# SCH-Display_Sheet_2_Altium.net
KiCad netlist of a schematic drawn in Altium Designer
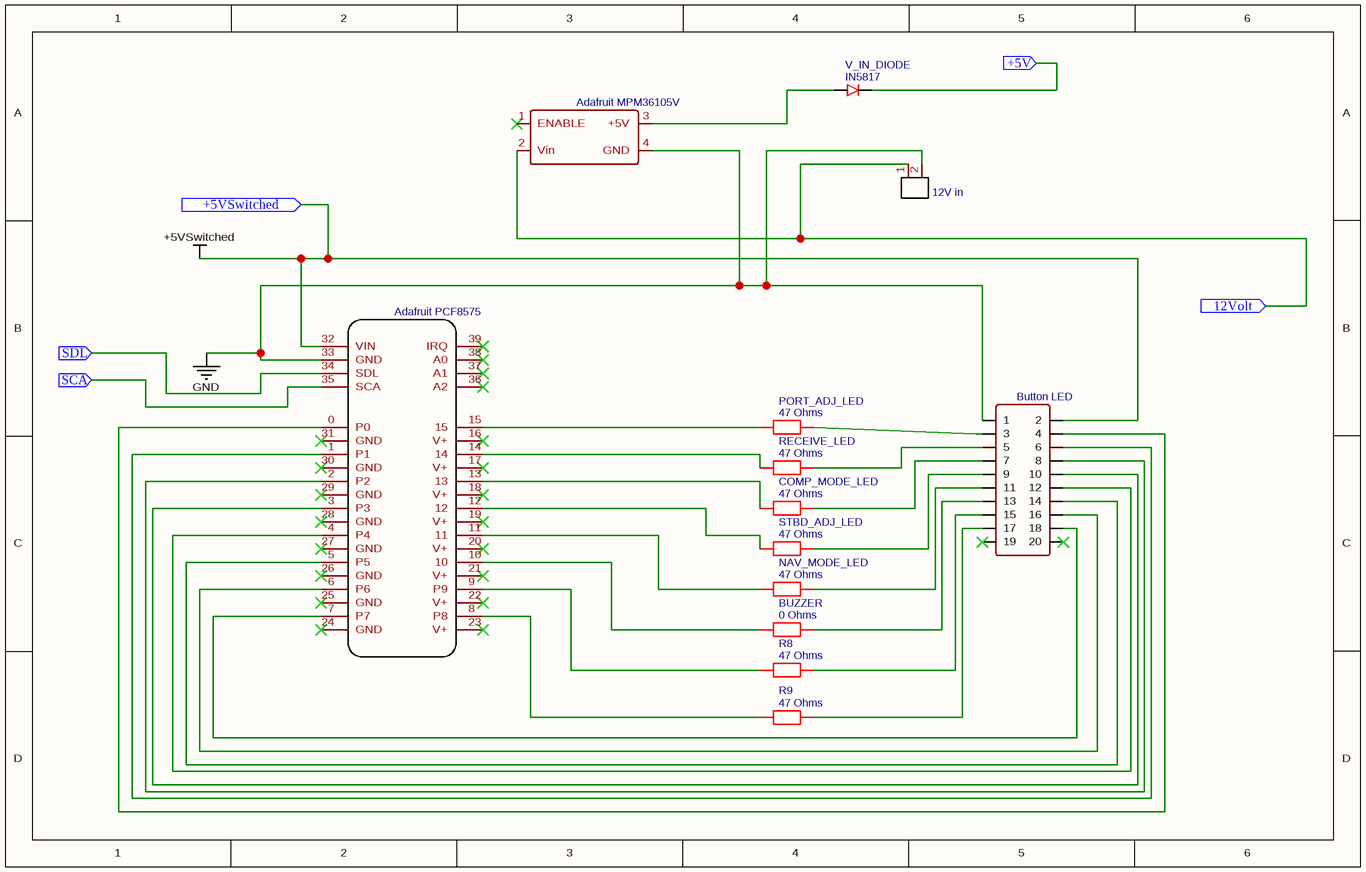
[diagram p0: SCH-Display_Sheet_2_Altium.schdoc]

(export (version "E")
  (design (tool "Eeschema 10.0.6"))
  (components
    (comp (ref "12V")
      (value "12V in")
      (fields (field (name "CONTRIBUTOR") "Grim Reaper (C0rbac)"))
      (libsource (lib "altium-import") (part "root_0_12V in_"))
    )
    (comp (ref "BUTTON_LED")
      (value "Button LED")
      (fields (field (name "CONTRIBUTOR") "LCEDA_Lib"))
      (libsource (lib "altium-import") (part "root_0_Button LED_"))
    )
    (comp (ref "BUZZER")
      (value "0 Ohms")
      (fields (field (name "CONTRIBUTOR") "Kagutsuchi"))
      (libsource (lib "altium-import") (part "root_0_0 Ohms_"))
    )
    (comp (ref "COMP_MODE_LED")
      (value "47 Ohms")
      (fields (field (name "CONTRIBUTOR") "Kagutsuchi"))
      (libsource (lib "altium-import") (part "root_0_47 Ohms_"))
    )
    (comp (ref "NAV_MODE_LED")
      (value "47 Ohms")
      (fields (field (name "CONTRIBUTOR") "Kagutsuchi"))
      (libsource (lib "altium-import") (part "root_0_47 Ohms_"))
    )
    (comp (ref "PORT_ADJ_LED")
      (value "47 Ohms")
      (fields (field (name "CONTRIBUTOR") "Kagutsuchi"))
      (libsource (lib "altium-import") (part "root_0_47 Ohms_"))
    )
    (comp (ref "R8")
      (value "47 Ohms")
      (fields (field (name "CONTRIBUTOR") "Kagutsuchi"))
      (libsource (lib "altium-import") (part "root_0_47 Ohms_"))
    )
    (comp (ref "R9")
      (value "47 Ohms")
      (fields (field (name "CONTRIBUTOR") "Kagutsuchi"))
      (libsource (lib "altium-import") (part "root_0_47 Ohms_"))
    )
    (comp (ref "RECEIVE_LED")
      (value "47 Ohms")
      (fields (field (name "CONTRIBUTOR") "Kagutsuchi"))
      (libsource (lib "altium-import") (part "root_0_47 Ohms_"))
    )
    (comp (ref "STBD_ADJ_LED")
      (value "47 Ohms")
      (fields (field (name "CONTRIBUTOR") "Kagutsuchi"))
      (libsource (lib "altium-import") (part "root_0_47 Ohms_"))
    )
    (comp (ref "U2")
      (value "Adafruit PCF8575")
      (fields (field (name "CONTRIBUTOR") "williambaucom"))
      (libsource (lib "altium-import") (part "root_3_Adafruit PCF8575_"))
    )
    (comp (ref "U5")
      (value "Adafruit MPM36105V")
      (fields (field (name "CONTRIBUTOR") "Aidan Farley"))
      (libsource (lib "altium-import") (part "root_0_Adafruit MPM36105V_"))
    )
    (comp (ref "V_IN_DIODE")
      (value "IN5817")
      (fields (field (name "MANUFACTURER PART") "DIODE") (field (name "CONTRIBUTOR") "mimit.oscar"))
      (libsource (lib "altium-import") (part "root_0_IN5817_"))
    )
  )
  (nets
    (net (code "1") (name "+5VSwitched") (class "Default")
      (node (ref "BUTTON_LED") (pin "2") (pinfunction "2_2") (pintype "passive"))
      (node (ref "U2") (pin "32") (pinfunction "VIN_32") (pintype "passive"))
    )
    (net (code "2") (name "/+5V") (class "Default")
      (node (ref "V_IN_DIODE") (pin "2") (pinfunction "2_2") (pintype "passive"))
    )
    (net (code "3") (name "/12Volt") (class "Default")
      (node (ref "12V") (pin "1") (pinfunction "1_1") (pintype "passive"))
      (node (ref "U5") (pin "2") (pinfunction "Vin_2") (pintype "passive"))
    )
    (net (code "4") (name "/SCA") (class "Default")
      (node (ref "U2") (pin "35") (pinfunction "SCA_35") (pintype "passive"))
    )
    (net (code "5") (name "/SDL") (class "Default")
      (node (ref "U2") (pin "34") (pinfunction "SDL_34") (pintype "passive"))
    )
    (net (code "6") (name "GND") (class "Default")
      (node (ref "12V") (pin "2") (pinfunction "2_2") (pintype "passive"))
      (node (ref "BUTTON_LED") (pin "1") (pinfunction "1_1") (pintype "passive"))
      (node (ref "U2") (pin "33") (pinfunction "GND_33") (pintype "passive"))
      (node (ref "U5") (pin "4") (pinfunction "GND_4") (pintype "passive"))
    )
    (net (code "7") (name "Net-(BUZZER-1)") (class "Default")
      (node (ref "BUTTON_LED") (pin "13") (pinfunction "13_13") (pintype "passive"))
      (node (ref "BUZZER") (pin "2") (pinfunction "1_2") (pintype "passive"))
    )
    (net (code "8") (name "Net-(BUZZER-2)") (class "Default")
      (node (ref "BUZZER") (pin "1") (pinfunction "2_1") (pintype "passive"))
      (node (ref "U2") (pin "10") (pinfunction "10_10") (pintype "passive"))
    )
    (net (code "9") (name "Net-(COMP_MODE_LED-1)") (class "Default")
      (node (ref "BUTTON_LED") (pin "7") (pinfunction "7_7") (pintype "passive"))
      (node (ref "COMP_MODE_LED") (pin "2") (pinfunction "1_2") (pintype "passive"))
    )
    (net (code "10") (name "Net-(COMP_MODE_LED-2)") (class "Default")
      (node (ref "COMP_MODE_LED") (pin "1") (pinfunction "2_1") (pintype "passive"))
      (node (ref "U2") (pin "13") (pinfunction "13_13") (pintype "passive"))
    )
    (net (code "11") (name "Net-(NAV_MODE_LED-1)") (class "Default")
      (node (ref "BUTTON_LED") (pin "11") (pinfunction "11_11") (pintype "passive"))
      (node (ref "NAV_MODE_LED") (pin "2") (pinfunction "1_2") (pintype "passive"))
    )
    (net (code "12") (name "Net-(NAV_MODE_LED-2)") (class "Default")
      (node (ref "NAV_MODE_LED") (pin "1") (pinfunction "2_1") (pintype "passive"))
      (node (ref "U2") (pin "11") (pinfunction "11_11") (pintype "passive"))
    )
    (net (code "13") (name "Net-(PORT_ADJ_LED-1)") (class "Default")
      (node (ref "BUTTON_LED") (pin "3") (pinfunction "3_3") (pintype "passive"))
      (node (ref "PORT_ADJ_LED") (pin "2") (pinfunction "1_2") (pintype "passive"))
    )
    (net (code "14") (name "Net-(PORT_ADJ_LED-2)") (class "Default")
      (node (ref "PORT_ADJ_LED") (pin "1") (pinfunction "2_1") (pintype "passive"))
      (node (ref "U2") (pin "15") (pinfunction "15_15") (pintype "passive"))
    )
    (net (code "15") (name "Net-(R8-1)") (class "Default")
      (node (ref "BUTTON_LED") (pin "15") (pinfunction "15_15") (pintype "passive"))
      (node (ref "R8") (pin "2") (pinfunction "1_2") (pintype "passive"))
    )
    (net (code "16") (name "Net-(R8-2)") (class "Default")
      (node (ref "R8") (pin "1") (pinfunction "2_1") (pintype "passive"))
      (node (ref "U2") (pin "9") (pinfunction "P9_9") (pintype "passive"))
    )
    (net (code "17") (name "Net-(R9-1)") (class "Default")
      (node (ref "BUTTON_LED") (pin "17") (pinfunction "17_17") (pintype "passive"))
      (node (ref "R9") (pin "2") (pinfunction "1_2") (pintype "passive"))
    )
    (net (code "18") (name "Net-(R9-2)") (class "Default")
      (node (ref "R9") (pin "1") (pinfunction "2_1") (pintype "passive"))
      (node (ref "U2") (pin "8") (pinfunction "P8_8") (pintype "passive"))
    )
    (net (code "19") (name "Net-(RECEIVE_LED-1)") (class "Default")
      (node (ref "BUTTON_LED") (pin "5") (pinfunction "5_5") (pintype "passive"))
      (node (ref "RECEIVE_LED") (pin "2") (pinfunction "1_2") (pintype "passive"))
    )
    (net (code "20") (name "Net-(RECEIVE_LED-2)") (class "Default")
      (node (ref "RECEIVE_LED") (pin "1") (pinfunction "2_1") (pintype "passive"))
      (node (ref "U2") (pin "14") (pinfunction "14_14") (pintype "passive"))
    )
    (net (code "21") (name "Net-(STBD_ADJ_LED-1)") (class "Default")
      (node (ref "BUTTON_LED") (pin "9") (pinfunction "9_9") (pintype "passive"))
      (node (ref "STBD_ADJ_LED") (pin "2") (pinfunction "1_2") (pintype "passive"))
    )
    (net (code "22") (name "Net-(STBD_ADJ_LED-2)") (class "Default")
      (node (ref "STBD_ADJ_LED") (pin "1") (pinfunction "2_1") (pintype "passive"))
      (node (ref "U2") (pin "12") (pinfunction "12_12") (pintype "passive"))
    )
    (net (code "23") (name "Net-(U2-P0)") (class "Default")
      (node (ref "BUTTON_LED") (pin "4") (pinfunction "4_4") (pintype "passive"))
      (node (ref "U2") (pin "0") (pinfunction "P0_0") (pintype "passive"))
    )
    (net (code "24") (name "Net-(U2-P1)") (class "Default")
      (node (ref "BUTTON_LED") (pin "6") (pinfunction "6_6") (pintype "passive"))
      (node (ref "U2") (pin "1") (pinfunction "P1_1") (pintype "passive"))
    )
    (net (code "25") (name "Net-(U2-P2)") (class "Default")
      (node (ref "BUTTON_LED") (pin "8") (pinfunction "8_8") (pintype "passive"))
      (node (ref "U2") (pin "2") (pinfunction "P2_2") (pintype "passive"))
    )
    (net (code "26") (name "Net-(U2-P3)") (class "Default")
      (node (ref "BUTTON_LED") (pin "10") (pinfunction "10_10") (pintype "passive"))
      (node (ref "U2") (pin "3") (pinfunction "P3_3") (pintype "passive"))
    )
    (net (code "27") (name "Net-(U2-P4)") (class "Default")
      (node (ref "BUTTON_LED") (pin "12") (pinfunction "12_12") (pintype "passive"))
      (node (ref "U2") (pin "4") (pinfunction "P4_4") (pintype "passive"))
    )
    (net (code "28") (name "Net-(U2-P5)") (class "Default")
      (node (ref "BUTTON_LED") (pin "14") (pinfunction "14_14") (pintype "passive"))
      (node (ref "U2") (pin "5") (pinfunction "P5_5") (pintype "passive"))
    )
    (net (code "29") (name "Net-(U2-P6)") (class "Default")
      (node (ref "BUTTON_LED") (pin "16") (pinfunction "16_16") (pintype "passive"))
      (node (ref "U2") (pin "6") (pinfunction "P6_6") (pintype "passive"))
    )
    (net (code "30") (name "Net-(U2-P7)") (class "Default")
      (node (ref "BUTTON_LED") (pin "18") (pinfunction "18_18") (pintype "passive"))
      (node (ref "U2") (pin "7") (pinfunction "P7_7") (pintype "passive"))
    )
    (net (code "31") (name "Net-(U5-+5V)") (class "Default")
      (node (ref "U5") (pin "3") (pinfunction "+5V_3") (pintype "passive"))
      (node (ref "V_IN_DIODE") (pin "1") (pinfunction "1_1") (pintype "passive"))
    )
    (net (code "32") (name "unconnected-(BUTTON_LED-Pad19)") (class "Default")
      (node (ref "BUTTON_LED") (pin "19") (pinfunction "19_19") (pintype "passive+no_connect"))
    )
    (net (code "33") (name "unconnected-(BUTTON_LED-Pad20)") (class "Default")
      (node (ref "BUTTON_LED") (pin "20") (pinfunction "20_20") (pintype "passive+no_connect"))
    )
    (net (code "34") (name "unconnected-(U2-A0-Pad38)") (class "Default")
      (node (ref "U2") (pin "38") (pinfunction "A0_38") (pintype "passive+no_connect"))
    )
    (net (code "35") (name "unconnected-(U2-A1-Pad37)") (class "Default")
      (node (ref "U2") (pin "37") (pinfunction "A1_37") (pintype "passive+no_connect"))
    )
    (net (code "36") (name "unconnected-(U2-A2-Pad36)") (class "Default")
      (node (ref "U2") (pin "36") (pinfunction "A2_36") (pintype "passive+no_connect"))
    )
    (net (code "37") (name "unconnected-(U2-GND-Pad24)") (class "Default")
      (node (ref "U2") (pin "24") (pinfunction "GND_24") (pintype "passive+no_connect"))
    )
    (net (code "38") (name "unconnected-(U2-GND-Pad25)") (class "Default")
      (node (ref "U2") (pin "25") (pinfunction "GND_25") (pintype "passive+no_connect"))
    )
    (net (code "39") (name "unconnected-(U2-GND-Pad26)") (class "Default")
      (node (ref "U2") (pin "26") (pinfunction "GND_26") (pintype "passive+no_connect"))
    )
    (net (code "40") (name "unconnected-(U2-GND-Pad27)") (class "Default")
      (node (ref "U2") (pin "27") (pinfunction "GND_27") (pintype "passive+no_connect"))
    )
    (net (code "41") (name "unconnected-(U2-GND-Pad28)") (class "Default")
      (node (ref "U2") (pin "28") (pinfunction "GND_28") (pintype "passive+no_connect"))
    )
    (net (code "42") (name "unconnected-(U2-GND-Pad29)") (class "Default")
      (node (ref "U2") (pin "29") (pinfunction "GND_29") (pintype "passive+no_connect"))
    )
    (net (code "43") (name "unconnected-(U2-GND-Pad30)") (class "Default")
      (node (ref "U2") (pin "30") (pinfunction "GND_30") (pintype "passive+no_connect"))
    )
    (net (code "44") (name "unconnected-(U2-GND-Pad31)") (class "Default")
      (node (ref "U2") (pin "31") (pinfunction "GND_31") (pintype "passive+no_connect"))
    )
    (net (code "45") (name "unconnected-(U2-IRQ-Pad39)") (class "Default")
      (node (ref "U2") (pin "39") (pinfunction "IRQ_39") (pintype "passive+no_connect"))
    )
    (net (code "46") (name "unconnected-(U2-V+-Pad16)") (class "Default")
      (node (ref "U2") (pin "16") (pinfunction "V+_16") (pintype "passive+no_connect"))
    )
    (net (code "47") (name "unconnected-(U2-V+-Pad17)") (class "Default")
      (node (ref "U2") (pin "17") (pinfunction "V+_17") (pintype "passive+no_connect"))
    )
    (net (code "48") (name "unconnected-(U2-V+-Pad18)") (class "Default")
      (node (ref "U2") (pin "18") (pinfunction "V+_18") (pintype "passive+no_connect"))
    )
    (net (code "49") (name "unconnected-(U2-V+-Pad19)") (class "Default")
      (node (ref "U2") (pin "19") (pinfunction "V+_19") (pintype "passive+no_connect"))
    )
    (net (code "50") (name "unconnected-(U2-V+-Pad20)") (class "Default")
      (node (ref "U2") (pin "20") (pinfunction "V+_20") (pintype "passive+no_connect"))
    )
    (net (code "51") (name "unconnected-(U2-V+-Pad21)") (class "Default")
      (node (ref "U2") (pin "21") (pinfunction "V+_21") (pintype "passive+no_connect"))
    )
    (net (code "52") (name "unconnected-(U2-V+-Pad22)") (class "Default")
      (node (ref "U2") (pin "22") (pinfunction "V+_22") (pintype "passive+no_connect"))
    )
    (net (code "53") (name "unconnected-(U2-V+-Pad23)") (class "Default")
      (node (ref "U2") (pin "23") (pinfunction "V+_23") (pintype "passive+no_connect"))
    )
    (net (code "54") (name "unconnected-(U5-ENABLE-Pad1)") (class "Default")
      (node (ref "U5") (pin "1") (pinfunction "ENABLE_1") (pintype "passive+no_connect"))
    )
  )
)
